# TMC5160A-DRIVER_Rev1.net
KiCad netlist of a schematic drawn in Altium Designer
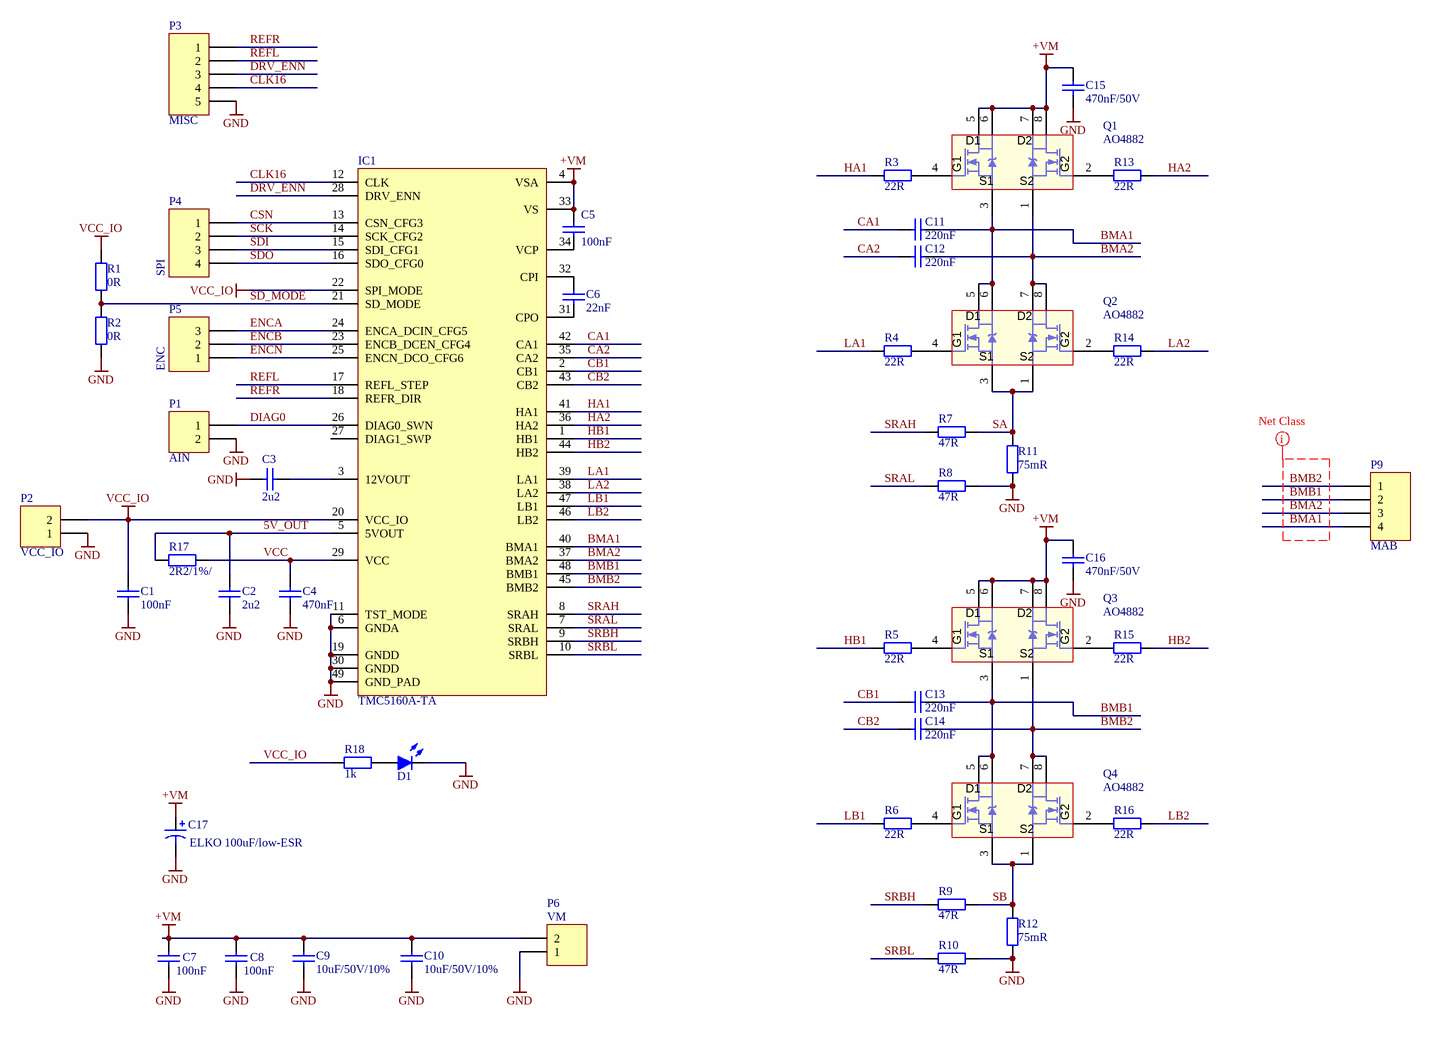
[diagram p0: TMC5160A-DRIVER_Rev1.SchDoc]

(export (version "E")
  (design (tool "Eeschema 10.0.6"))
  (components
    (comp (ref "C1")
      (value "100nF")
      (footprint "C0603")
      (description "Ceramic capacitor")
      (fields (field (name "MANUFACTURER") "Multicomp") (field (name "MPN") "MC0603F104M500CT"))
      (libsource (lib "SCH Passives") (part "Capacitor"))
    )
    (comp (ref "C2")
      (value "2u2")
      (footprint "C0603")
      (description "SMD Multilayer Ceramic Capacitor, 0603 [1608 Metric], 2.2 µF, 25 V, ± 10%, X5R, GRM Series")
      (fields (field (name "MF") "MURATA") (field (name "MPN") "GRM188R61E225KA12D"))
      (libsource (lib "TMC5160_RevA") (part "2.2 µF, 25 V, ± 10%, X5R, GRM Series"))
    )
    (comp (ref "C3")
      (value "2u2")
      (footprint "C0603")
      (description "SMD Multilayer Ceramic Capacitor, 0603 [1608 Metric], 2.2 µF, 25 V, ± 10%, X5R, GRM Series")
      (fields (field (name "MF") "MURATA") (field (name "MPN") "GRM188R61E225KA12D"))
      (libsource (lib "TMC5160_RevA") (part "2.2 µF, 25 V, ± 10%, X5R, GRM Series"))
    )
    (comp (ref "C4")
      (value "470nF")
      (footprint "C0603")
      (description "Ceramic capacitor")
      (fields (field (name "MF") "Multicomp") (field (name "MPN") "MC0603X474K160CT"))
      (libsource (lib "SCH Passives") (part "Capacitor"))
    )
    (comp (ref "C5")
      (value "100nF")
      (footprint "C0603")
      (description "Ceramic capacitor")
      (fields (field (name "MF") "Multicomp") (field (name "MPN") "MC0603F104M500CT"))
      (libsource (lib "SCH Passives") (part "Capacitor"))
    )
    (comp (ref "C6")
      (value "22nF")
      (footprint "C0603")
      (description "Ceramic capacitor")
      (fields (field (name "MF") "Multicomp") (field (name "MPN") "MC0603B223K500CT"))
      (libsource (lib "SCH Passives") (part "Capacitor"))
    )
    (comp (ref "C7")
      (value "100nF")
      (footprint "C0603")
      (description "Ceramic capacitor")
      (fields (field (name "MANUFACTURER") "Multicomp") (field (name "MPN") "MC0603F104M500CT"))
      (libsource (lib "SCH Passives") (part "Capacitor"))
    )
    (comp (ref "C8")
      (value "100nF")
      (footprint "C0603")
      (description "Ceramic capacitor")
      (fields (field (name "MANUFACTURER") "Multicomp") (field (name "MPN") "MC0603F104M500CT"))
      (libsource (lib "SCH Passives") (part "Capacitor"))
    )
    (comp (ref "C9")
      (value "10uF/50V/10%")
      (footprint "C1206")
      (description "SMD Multilayer Ceramic Capacitor, 1206 [3216 Metric], 10 µF, 50 V, ± 20%, X5R, GRM Series")
      (fields (field (name "MF") "MURATA") (field (name "MPN") "GRM31CR61H106MA12L"))
      (libsource (lib "TMC262_FDD8424H_RevA") (part "10 µF, 50 V, ± 20%, X5R, GRM Series"))
    )
    (comp (ref "C10")
      (value "10uF/50V/10%")
      (footprint "C1206")
      (description "SMD Multilayer Ceramic Capacitor, 1206 [3216 Metric], 10 µF, 50 V, ± 20%, X5R, GRM Series")
      (fields (field (name "MF") "MURATA") (field (name "MPN") "GRM31CR61H106MA12L"))
      (libsource (lib "TMC262_FDD8424H_RevA") (part "10 µF, 50 V, ± 20%, X5R, GRM Series"))
    )
    (comp (ref "C11")
      (value "220nF")
      (footprint "C0603")
      (description "SMD Multilayer Ceramic Capacitor, 0603 [1608 Metric], 0.22 µF, 50 V, ± 10%, X7R, GCM Series")
      (fields (field (name "MF") "MURATA") (field (name "MPN") "GCM188R71H224KA64D"))
      (libsource (lib "TMC5160_RevA") (part "0.22 µF, 50 V, ± 10%, X7R"))
    )
    (comp (ref "C12")
      (value "220nF")
      (footprint "C0603")
      (description "SMD Multilayer Ceramic Capacitor, 0603 [1608 Metric], 0.22 µF, 50 V, ± 10%, X7R, GCM Series")
      (fields (field (name "MF") "MURATA") (field (name "MPN") "GCM188R71H224KA64D"))
      (libsource (lib "TMC5160_RevA") (part "0.22 µF, 50 V, ± 10%, X7R"))
    )
    (comp (ref "C13")
      (value "220nF")
      (footprint "C0603")
      (description "SMD Multilayer Ceramic Capacitor, 0603 [1608 Metric], 0.22 µF, 50 V, ± 10%, X7R, GCM Series")
      (fields (field (name "MF") "MURATA") (field (name "MPN") "GCM188R71H224KA64D"))
      (libsource (lib "TMC5160_RevA") (part "0.22 µF, 50 V, ± 10%, X7R"))
    )
    (comp (ref "C14")
      (value "220nF")
      (footprint "C0603")
      (description "SMD Multilayer Ceramic Capacitor, 0603 [1608 Metric], 0.22 µF, 50 V, ± 10%, X7R, GCM Series")
      (fields (field (name "MF") "MURATA") (field (name "MPN") "GCM188R71H224KA64D"))
      (libsource (lib "TMC5160_RevA") (part "0.22 µF, 50 V, ± 10%, X7R"))
    )
    (comp (ref "C15")
      (value "470nF/50V")
      (footprint "C0603")
      (description "SMD Multilayer Ceramic Capacitor, 0603 [1608 Metric], 0.47 µF, 50 V, ± 10%, X7R, C Series")
      (fields (field (name "MF") "TDK") (field (name "MPN") "C1608X7R1H474K080AC"))
      (libsource (lib "TMC5160_RevA") (part "0.47 µF, 50 V, ± 10%, X7R, C Series"))
    )
    (comp (ref "C16")
      (value "470nF/50V")
      (footprint "C0603")
      (description "SMD Multilayer Ceramic Capacitor, 0603 [1608 Metric], 0.47 µF, 50 V, ± 10%, X7R, C Series")
      (fields (field (name "MF") "TDK") (field (name "MPN") "C1608X7R1H474K080AC"))
      (libsource (lib "TMC5160_RevA") (part "0.47 µF, 50 V, ± 10%, X7R, C Series"))
    )
    (comp (ref "C17")
      (value "ELKO 100uF/low-ESR")
      (footprint "EXT_POL_CAP")
      (description "Polarized Capacitor (Radial)")
      (fields (field (name "Comment") "Cap Pol1") (field (name "PUBLISHER") "Altium Limited"))
      (libsource (lib "Miscellaneous Devices") (part "Cap Pol1"))
    )
    (comp (ref "D1")
      (value "LED, Blue, SMD, 20mA, 2.8V, 465 nm")
      (footprint "LED_0603")
      (fields (field (name "MF") "Lite-On") (field (name "MPN") "LTST-C191TBKT-5A"))
      (libsource (lib "TMC26x_RevA") (part "LED, Blue, SMD, 20mA, 2.8V, 465 nm"))
    )
    (comp (ref "IC1")
      (value "TMC5160A-TA")
      (footprint "TMC5160_TSQFP50P900X900X120_HS-49L")
      (fields (field (name "MANUFACTURER") "TRINAMIC"))
      (libsource (lib "TMC5160_BOB_V1_2") (part "TMC5160-TA"))
    )
    (comp (ref "P1")
      (value "AIN")
      (footprint "2_PIN_THT")
      (description "Header, 2-Pin")
      (fields (field (name "PUBLISHER") "Altium Limited"))
      (libsource (lib "Miscellaneous Connectors") (part "Header 2"))
    )
    (comp (ref "P2")
      (value "VCC_IO")
      (footprint "2_PIN_THT")
      (description "Header, 2-Pin")
      (fields (field (name "PUBLISHER") "Altium Limited"))
      (libsource (lib "") (part "Header 2_1"))
    )
    (comp (ref "P3")
      (value "MISC")
      (footprint "5_PIN_THT")
      (description "Header, 5-Pin")
      (fields (field (name "PUBLISHER") "Altium Limited"))
      (libsource (lib "Miscellaneous Connectors") (part "Header 5"))
    )
    (comp (ref "P4")
      (value "SPI")
      (footprint "4_PIN_THT")
      (description "Header, 4-Pin")
      (fields (field (name "PUBLISHER") "Altium Limited"))
      (libsource (lib "Miscellaneous Connectors") (part "Header 4"))
    )
    (comp (ref "P5")
      (value "ENC")
      (footprint "3_PIN_THT")
      (description "Header, 3-Pin")
      (fields (field (name "PUBLISHER") "Altium Limited"))
      (libsource (lib "Miscellaneous Connectors") (part "Header 3"))
    )
    (comp (ref "P6")
      (value "VM")
      (footprint "2_PIN_THT")
      (description "Header, 2-Pin")
      (fields (field (name "PUBLISHER") "Altium Limited"))
      (libsource (lib "") (part "Header 2_2"))
    )
    (comp (ref "P9")
      (value "MAB")
      (footprint "4_PIN_THT_1mm_hole")
      (description "Wire-To-Board Connector, 2.5 mm, 4 Contacts, Header, EH Series, Through Hole, 1 Rows")
      (fields (field (name "MPN") "B4B-EH-A") (field (name "MF") "JST (JAPAN SOLDERLESS TERMINALS)"))
      (libsource (lib "TMC5160_RevA") (part "Wire-To-Board Connector, 2.5 mm, 4 Contacts, Header, EH Series, Through Hole, 1 Rows"))
    )
    (comp (ref "Q1")
      (value "AO4882")
      (footprint "SOP127P600X170-8L")
      (description "Mosfet Array 2 N-Channel (Dual) 40V 8A 2W Surface Mount 8-SOIC")
      (fields (field (name "MF") "Alpha & Omega Semiconductor Inc."))
      (libsource (lib "TMC5160_RevA") (part "AO4882 MOSFET 2N-CH 40V 8A 8SOIC"))
    )
    (comp (ref "Q2")
      (value "AO4882")
      (footprint "SOP127P600X170-8L")
      (description "Mosfet Array 2 N-Channel (Dual) 40V 8A 2W Surface Mount 8-SOIC")
      (fields (field (name "MF") "Alpha & Omega Semiconductor Inc."))
      (libsource (lib "TMC5160_RevA") (part "AO4882 MOSFET 2N-CH 40V 8A 8SOIC"))
    )
    (comp (ref "Q3")
      (value "AO4882")
      (footprint "SOP127P600X170-8L")
      (description "Mosfet Array 2 N-Channel (Dual) 40V 8A 2W Surface Mount 8-SOIC")
      (fields (field (name "MF") "Alpha & Omega Semiconductor Inc."))
      (libsource (lib "TMC5160_RevA") (part "AO4882 MOSFET 2N-CH 40V 8A 8SOIC"))
    )
    (comp (ref "Q4")
      (value "AO4882")
      (footprint "SOP127P600X170-8L")
      (description "Mosfet Array 2 N-Channel (Dual) 40V 8A 2W Surface Mount 8-SOIC")
      (fields (field (name "MF") "Alpha & Omega Semiconductor Inc."))
      (libsource (lib "TMC5160_RevA") (part "AO4882 MOSFET 2N-CH 40V 8A 8SOIC"))
    )
    (comp (ref "R1")
      (value "0R")
      (footprint "R0603")
      (description "SMD Chip Resistor, Thick Film, 0 ohm, 0603 [1608 Metric], 100 mW, MCWR Series")
      (fields
        (field (name "MPN") "MCWR06X000 PTL")
        (field (name "MF") "MULTICOMP")
        (field (name "RESISTANCE") "0R")
      )
      (libsource (lib "TMC5160_RevA") (part "0 ohm, 0603 [1608 Metric], 100 mW, MCWR Series"))
    )
    (comp (ref "R2")
      (value "0R")
      (footprint "R0603")
      (description "SMD Chip Resistor, Thick Film, 0 ohm, 0603 [1608 Metric], 100 mW, MCWR Series")
      (fields
        (field (name "MPN") "MCWR06X000 PTL")
        (field (name "MF") "MULTICOMP")
        (field (name "RESISTANCE") "0R")
      )
      (libsource (lib "TMC5160_RevA") (part "0 ohm, 0603 [1608 Metric], 100 mW, MCWR Series"))
    )
    (comp (ref "R3")
      (value "22R / 100mW / 1%")
      (footprint "R0603")
      (description "SMD Chip Resistor, Thick Film, 22 ohm, 50 V, 0603 [1608 Metric], 100 mW, ± 1%, MCWR Series")
      (fields
        (field (name "MPN") "MCWR06X22R0FTLV")
        (field (name "MF") "MULTICOMP")
        (field (name "RESISTANCE") "22R")
      )
      (libsource (lib "TMC5160_RevA") (part "22 ohm, 50 V, 0603 [1608 Metric], 100 mW, ± 1%, MCWR Series"))
    )
    (comp (ref "R4")
      (value "22R / 100mW / 1%")
      (footprint "R0603")
      (description "SMD Chip Resistor, Thick Film, 22 ohm, 50 V, 0603 [1608 Metric], 100 mW, ± 1%, MCWR Series")
      (fields
        (field (name "MPN") "MCWR06X22R0FTLV")
        (field (name "MF") "MULTICOMP")
        (field (name "RESISTANCE") "22R")
      )
      (libsource (lib "TMC5160_RevA") (part "22 ohm, 50 V, 0603 [1608 Metric], 100 mW, ± 1%, MCWR Series"))
    )
    (comp (ref "R5")
      (value "22R / 100mW / 1%")
      (footprint "R0603")
      (description "SMD Chip Resistor, Thick Film, 22 ohm, 50 V, 0603 [1608 Metric], 100 mW, ± 1%, MCWR Series")
      (fields
        (field (name "MPN") "MCWR06X22R0FTLV")
        (field (name "MF") "MULTICOMP")
        (field (name "RESISTANCE") "22R")
      )
      (libsource (lib "TMC5160_RevA") (part "22 ohm, 50 V, 0603 [1608 Metric], 100 mW, ± 1%, MCWR Series"))
    )
    (comp (ref "R6")
      (value "22R / 100mW / 1%")
      (footprint "R0603")
      (description "SMD Chip Resistor, Thick Film, 22 ohm, 50 V, 0603 [1608 Metric], 100 mW, ± 1%, MCWR Series")
      (fields
        (field (name "MPN") "MCWR06X22R0FTLV")
        (field (name "MF") "MULTICOMP")
        (field (name "RESISTANCE") "22R")
      )
      (libsource (lib "TMC5160_RevA") (part "22 ohm, 50 V, 0603 [1608 Metric], 100 mW, ± 1%, MCWR Series"))
    )
    (comp (ref "R7")
      (value "47R /  / 1%")
      (footprint "R0603")
      (description "SMD Chip Resistor, Ceramic, 47 ohm, 75 V, 0603 [1608 Metric], 100 mW, ± 1%, MCSR 06 Series")
      (fields
        (field (name "MPN") "MCSR06X47R0FTL")
        (field (name "MF") "MULTICOMP")
        (field (name "RESISTANCE") "47R")
      )
      (libsource (lib "TMC5160_RevA") (part "47 ohm, 75 V, 0603 [1608 Metric], 100 mW, ± 1%, MCSR 06 Series"))
    )
    (comp (ref "R8")
      (value "47R /  / 1%")
      (footprint "R0603")
      (description "SMD Chip Resistor, Ceramic, 47 ohm, 75 V, 0603 [1608 Metric], 100 mW, ± 1%, MCSR 06 Series")
      (fields
        (field (name "MPN") "MCSR06X47R0FTL")
        (field (name "MF") "MULTICOMP")
        (field (name "RESISTANCE") "47R")
      )
      (libsource (lib "TMC5160_RevA") (part "47 ohm, 75 V, 0603 [1608 Metric], 100 mW, ± 1%, MCSR 06 Series"))
    )
    (comp (ref "R9")
      (value "47R /  / 1%")
      (footprint "R0603")
      (description "SMD Chip Resistor, Ceramic, 47 ohm, 75 V, 0603 [1608 Metric], 100 mW, ± 1%, MCSR 06 Series")
      (fields
        (field (name "MPN") "MCSR06X47R0FTL")
        (field (name "MF") "MULTICOMP")
        (field (name "RESISTANCE") "47R")
      )
      (libsource (lib "TMC5160_RevA") (part "47 ohm, 75 V, 0603 [1608 Metric], 100 mW, ± 1%, MCSR 06 Series"))
    )
    (comp (ref "R10")
      (value "47R /  / 1%")
      (footprint "R0603")
      (description "SMD Chip Resistor, Ceramic, 47 ohm, 75 V, 0603 [1608 Metric], 100 mW, ± 1%, MCSR 06 Series")
      (fields
        (field (name "MPN") "MCSR06X47R0FTL")
        (field (name "MF") "MULTICOMP")
        (field (name "RESISTANCE") "47R")
      )
      (libsource (lib "TMC5160_RevA") (part "47 ohm, 75 V, 0603 [1608 Metric], 100 mW, ± 1%, MCSR 06 Series"))
    )
    (comp (ref "R11")
      (value "75mR")
      (footprint "R1206")
      (description "SMD Chip Resistor, Thick Film, Current Sense Resistors - SMD 1W 0.075ohm 1%")
      (fields
        (field (name "MPN") "ERJ-8BWFR075V")
        (field (name "MF") "Panasonic Electronic Components")
        (field (name "RESISTANCE") "75mR")
      )
      (libsource (lib "SMD_Passives") (part "R_SENS, 0.075 ohm, 1206, 1W, ± 1%, ERJ Series"))
    )
    (comp (ref "R12")
      (value "75mR")
      (footprint "R1206")
      (description "SMD Chip Resistor, Thick Film, Current Sense Resistors - SMD 1W 0.075ohm 1%")
      (fields
        (field (name "MPN") "ERJ-8BWFR075V")
        (field (name "MF") "Panasonic Electronic Components")
        (field (name "RESISTANCE") "75mR")
      )
      (libsource (lib "SMD_Passives") (part "R_SENS, 0.075 ohm, 1206, 1W, ± 1%, ERJ Series"))
    )
    (comp (ref "R13")
      (value "22R / 100mW / 1%")
      (footprint "R0603")
      (description "SMD Chip Resistor, Thick Film, 22 ohm, 50 V, 0603 [1608 Metric], 100 mW, ± 1%, MCWR Series")
      (fields
        (field (name "MPN") "MCWR06X22R0FTLV")
        (field (name "MF") "MULTICOMP")
        (field (name "RESISTANCE") "22R")
      )
      (libsource (lib "TMC5160_RevA") (part "22 ohm, 50 V, 0603 [1608 Metric], 100 mW, ± 1%, MCWR Series"))
    )
    (comp (ref "R14")
      (value "22R / 100mW / 1%")
      (footprint "R0603")
      (description "SMD Chip Resistor, Thick Film, 22 ohm, 50 V, 0603 [1608 Metric], 100 mW, ± 1%, MCWR Series")
      (fields
        (field (name "MPN") "MCWR06X22R0FTLV")
        (field (name "MF") "MULTICOMP")
        (field (name "RESISTANCE") "22R")
      )
      (libsource (lib "TMC5160_RevA") (part "22 ohm, 50 V, 0603 [1608 Metric], 100 mW, ± 1%, MCWR Series"))
    )
    (comp (ref "R15")
      (value "22R / 100mW / 1%")
      (footprint "R0603")
      (description "SMD Chip Resistor, Thick Film, 22 ohm, 50 V, 0603 [1608 Metric], 100 mW, ± 1%, MCWR Series")
      (fields
        (field (name "MPN") "MCWR06X22R0FTLV")
        (field (name "MF") "MULTICOMP")
        (field (name "RESISTANCE") "22R")
      )
      (libsource (lib "TMC5160_RevA") (part "22 ohm, 50 V, 0603 [1608 Metric], 100 mW, ± 1%, MCWR Series"))
    )
    (comp (ref "R16")
      (value "22R / 100mW / 1%")
      (footprint "R0603")
      (description "SMD Chip Resistor, Thick Film, 22 ohm, 50 V, 0603 [1608 Metric], 100 mW, ± 1%, MCWR Series")
      (fields
        (field (name "MPN") "MCWR06X22R0FTLV")
        (field (name "MF") "MULTICOMP")
        (field (name "RESISTANCE") "22R")
      )
      (libsource (lib "TMC5160_RevA") (part "22 ohm, 50 V, 0603 [1608 Metric], 100 mW, ± 1%, MCWR Series"))
    )
    (comp (ref "R17")
      (value "2R2/1%/")
      (footprint "R0603")
      (description "Resistor")
      (fields (field (name "MPN") "MC0063W060312R2") (field (name "MF") "Multicomp"))
      (libsource (lib "SCH Passives") (part "Resistor"))
    )
    (comp (ref "R18")
      (value "1k")
      (footprint "R0603")
      (description "1 kohm, 50 V, 0603 [1608 Metric], 63 mW, ± 1%, MC Series")
      (fields
        (field (name "MPN") "MC0063W060311K")
        (field (name "MF") "MULTICOMP")
        (field (name "RESISTANCE") "1k")
      )
      (libsource (lib "TMC457_RevA") (part "1 kohm, 50 V, 0603 [1608 Metric], 63 mW, ± 1%, MC Series"))
    )
  )
  (nets
    (net (code "1") (name "+VM") (class "Default")
      (node (ref "C10") (pin "2") (pinfunction "2_2") (pintype "passive"))
      (node (ref "C15") (pin "1") (pinfunction "1_1") (pintype "passive"))
      (node (ref "C16") (pin "1") (pinfunction "1_1") (pintype "passive"))
      (node (ref "C17") (pin "1") (pinfunction "1_1") (pintype "passive"))
      (node (ref "C5") (pin "1") (pinfunction "1_1") (pintype "passive"))
      (node (ref "C7") (pin "1") (pinfunction "1_1") (pintype "passive"))
      (node (ref "C8") (pin "1") (pinfunction "1_1") (pintype "passive"))
      (node (ref "C9") (pin "2") (pinfunction "2_2") (pintype "passive"))
      (node (ref "IC1") (pin "33") (pinfunction "VS_33") (pintype "passive"))
      (node (ref "IC1") (pin "4") (pinfunction "VSA_4") (pintype "passive"))
      (node (ref "P6") (pin "2") (pinfunction "2_2") (pintype "passive"))
      (node (ref "Q1") (pin "5") (pinfunction "D1_5") (pintype "passive"))
      (node (ref "Q1") (pin "6") (pinfunction "D1_6") (pintype "passive"))
      (node (ref "Q1") (pin "7") (pinfunction "D2_7") (pintype "passive"))
      (node (ref "Q1") (pin "8") (pinfunction "D2_8") (pintype "passive"))
      (node (ref "Q3") (pin "5") (pinfunction "D1_5") (pintype "passive"))
      (node (ref "Q3") (pin "6") (pinfunction "D1_6") (pintype "passive"))
      (node (ref "Q3") (pin "7") (pinfunction "D2_7") (pintype "passive"))
      (node (ref "Q3") (pin "8") (pinfunction "D2_8") (pintype "passive"))
    )
    (net (code "2") (name "/5V_OUT") (class "Default")
      (node (ref "C2") (pin "1") (pinfunction "1_1") (pintype "passive"))
      (node (ref "IC1") (pin "5") (pinfunction "5VOUT_5") (pintype "passive"))
      (node (ref "R17") (pin "1") (pinfunction "1_1") (pintype "passive"))
    )
    (net (code "3") (name "/BMA1") (class "Default")
      (node (ref "C11") (pin "2") (pinfunction "2_2") (pintype "passive"))
      (node (ref "IC1") (pin "40") (pinfunction "BMA1_40") (pintype "passive"))
      (node (ref "P9") (pin "4") (pinfunction "4_4") (pintype "passive"))
      (node (ref "Q1") (pin "3") (pinfunction "S1_3") (pintype "passive"))
      (node (ref "Q2") (pin "5") (pinfunction "D1_5") (pintype "passive"))
      (node (ref "Q2") (pin "6") (pinfunction "D1_6") (pintype "passive"))
    )
    (net (code "4") (name "/BMA2") (class "Default")
      (node (ref "C12") (pin "2") (pinfunction "2_2") (pintype "passive"))
      (node (ref "IC1") (pin "37") (pinfunction "BMA2_37") (pintype "passive"))
      (node (ref "P9") (pin "3") (pinfunction "3_3") (pintype "passive"))
      (node (ref "Q1") (pin "1") (pinfunction "S2_1") (pintype "passive"))
      (node (ref "Q2") (pin "7") (pinfunction "D2_7") (pintype "passive"))
      (node (ref "Q2") (pin "8") (pinfunction "D2_8") (pintype "passive"))
    )
    (net (code "5") (name "/BMB1") (class "Default")
      (node (ref "C13") (pin "2") (pinfunction "2_2") (pintype "passive"))
      (node (ref "IC1") (pin "48") (pinfunction "BMB1_48") (pintype "passive"))
      (node (ref "P9") (pin "2") (pinfunction "2_2") (pintype "passive"))
      (node (ref "Q3") (pin "3") (pinfunction "S1_3") (pintype "passive"))
      (node (ref "Q4") (pin "5") (pinfunction "D1_5") (pintype "passive"))
      (node (ref "Q4") (pin "6") (pinfunction "D1_6") (pintype "passive"))
    )
    (net (code "6") (name "/BMB2") (class "Default")
      (node (ref "C14") (pin "2") (pinfunction "2_2") (pintype "passive"))
      (node (ref "IC1") (pin "45") (pinfunction "BMB2_45") (pintype "passive"))
      (node (ref "P9") (pin "1") (pinfunction "1_1") (pintype "passive"))
      (node (ref "Q3") (pin "1") (pinfunction "S2_1") (pintype "passive"))
      (node (ref "Q4") (pin "7") (pinfunction "D2_7") (pintype "passive"))
      (node (ref "Q4") (pin "8") (pinfunction "D2_8") (pintype "passive"))
    )
    (net (code "7") (name "/CA1") (class "Default")
      (node (ref "C11") (pin "1") (pinfunction "1_1") (pintype "passive"))
      (node (ref "IC1") (pin "42") (pinfunction "CA1_42") (pintype "passive"))
    )
    (net (code "8") (name "/CA2") (class "Default")
      (node (ref "C12") (pin "1") (pinfunction "1_1") (pintype "passive"))
      (node (ref "IC1") (pin "35") (pinfunction "CA2_35") (pintype "passive"))
    )
    (net (code "9") (name "/CB1") (class "Default")
      (node (ref "C13") (pin "1") (pinfunction "1_1") (pintype "passive"))
      (node (ref "IC1") (pin "2") (pinfunction "CB1_2") (pintype "passive"))
    )
    (net (code "10") (name "/CB2") (class "Default")
      (node (ref "C14") (pin "1") (pinfunction "1_1") (pintype "passive"))
      (node (ref "IC1") (pin "43") (pinfunction "CB2_43") (pintype "passive"))
    )
    (net (code "11") (name "/CLK16") (class "Default")
      (node (ref "IC1") (pin "12") (pinfunction "CLK_12") (pintype "passive"))
      (node (ref "P3") (pin "4") (pinfunction "4_4") (pintype "passive"))
    )
    (net (code "12") (name "/CSN") (class "Default")
      (node (ref "IC1") (pin "13") (pinfunction "CSN_CFG3_13") (pintype "passive"))
      (node (ref "P4") (pin "1") (pinfunction "1_1") (pintype "passive"))
    )
    (net (code "13") (name "/DIAG0") (class "Default")
      (node (ref "IC1") (pin "26") (pinfunction "DIAG0_SWN_26") (pintype "passive"))
      (node (ref "P1") (pin "1") (pinfunction "1_1") (pintype "passive"))
    )
    (net (code "14") (name "/DRV_ENN") (class "Default")
      (node (ref "IC1") (pin "28") (pinfunction "DRV_ENN_28") (pintype "passive"))
      (node (ref "P3") (pin "3") (pinfunction "3_3") (pintype "passive"))
    )
    (net (code "15") (name "/ENCA") (class "Default")
      (node (ref "IC1") (pin "24") (pinfunction "ENCA_DCIN_CFG5_24") (pintype "passive"))
      (node (ref "P5") (pin "3") (pinfunction "3_3") (pintype "passive"))
    )
    (net (code "16") (name "/ENCB") (class "Default")
      (node (ref "IC1") (pin "23") (pinfunction "ENCB_DCEN_CFG4_23") (pintype "passive"))
      (node (ref "P5") (pin "2") (pinfunction "2_2") (pintype "passive"))
    )
    (net (code "17") (name "/ENCN") (class "Default")
      (node (ref "IC1") (pin "25") (pinfunction "ENCN_DCO_CFG6_25") (pintype "passive"))
      (node (ref "P5") (pin "1") (pinfunction "1_1") (pintype "passive"))
    )
    (net (code "18") (name "/HA1") (class "Default")
      (node (ref "IC1") (pin "41") (pinfunction "HA1_41") (pintype "passive"))
      (node (ref "R3") (pin "2") (pinfunction "2_2") (pintype "passive"))
    )
    (net (code "19") (name "/HA2") (class "Default")
      (node (ref "IC1") (pin "36") (pinfunction "HA2_36") (pintype "passive"))
      (node (ref "R13") (pin "1") (pinfunction "1_1") (pintype "passive"))
    )
    (net (code "20") (name "/HB1") (class "Default")
      (node (ref "IC1") (pin "1") (pinfunction "HB1_1") (pintype "passive"))
      (node (ref "R5") (pin "2") (pinfunction "2_2") (pintype "passive"))
    )
    (net (code "21") (name "/HB2") (class "Default")
      (node (ref "IC1") (pin "44") (pinfunction "HB2_44") (pintype "passive"))
      (node (ref "R15") (pin "1") (pinfunction "1_1") (pintype "passive"))
    )
    (net (code "22") (name "/LA1") (class "Default")
      (node (ref "IC1") (pin "39") (pinfunction "LA1_39") (pintype "passive"))
      (node (ref "R4") (pin "2") (pinfunction "2_2") (pintype "passive"))
    )
    (net (code "23") (name "/LA2") (class "Default")
      (node (ref "IC1") (pin "38") (pinfunction "LA2_38") (pintype "passive"))
      (node (ref "R14") (pin "1") (pinfunction "1_1") (pintype "passive"))
    )
    (net (code "24") (name "/LB1") (class "Default")
      (node (ref "IC1") (pin "47") (pinfunction "LB1_47") (pintype "passive"))
      (node (ref "R6") (pin "2") (pinfunction "2_2") (pintype "passive"))
    )
    (net (code "25") (name "/LB2") (class "Default")
      (node (ref "IC1") (pin "46") (pinfunction "LB2_46") (pintype "passive"))
      (node (ref "R16") (pin "1") (pinfunction "1_1") (pintype "passive"))
    )
    (net (code "26") (name "/REFL") (class "Default")
      (node (ref "IC1") (pin "17") (pinfunction "REFL_STEP_17") (pintype "passive"))
      (node (ref "P3") (pin "2") (pinfunction "2_2") (pintype "passive"))
    )
    (net (code "27") (name "/REFR") (class "Default")
      (node (ref "IC1") (pin "18") (pinfunction "REFR_DIR_18") (pintype "passive"))
      (node (ref "P3") (pin "1") (pinfunction "1_1") (pintype "passive"))
    )
    (net (code "28") (name "/SA") (class "Default")
      (node (ref "Q2") (pin "1") (pinfunction "S2_1") (pintype "passive"))
      (node (ref "Q2") (pin "3") (pinfunction "S1_3") (pintype "passive"))
      (node (ref "R11") (pin "1") (pinfunction "1_1") (pintype "passive"))
      (node (ref "R7") (pin "1") (pinfunction "1_1") (pintype "passive"))
    )
    (net (code "29") (name "/SB") (class "Default")
      (node (ref "Q4") (pin "1") (pinfunction "S2_1") (pintype "passive"))
      (node (ref "Q4") (pin "3") (pinfunction "S1_3") (pintype "passive"))
      (node (ref "R12") (pin "1") (pinfunction "1_1") (pintype "passive"))
      (node (ref "R9") (pin "1") (pinfunction "1_1") (pintype "passive"))
    )
    (net (code "30") (name "/SCK") (class "Default")
      (node (ref "IC1") (pin "14") (pinfunction "SCK_CFG2_14") (pintype "passive"))
      (node (ref "P4") (pin "2") (pinfunction "2_2") (pintype "passive"))
    )
    (net (code "31") (name "/SDI") (class "Default")
      (node (ref "IC1") (pin "15") (pinfunction "SDI_CFG1_15") (pintype "passive"))
      (node (ref "P4") (pin "3") (pinfunction "3_3") (pintype "passive"))
    )
    (net (code "32") (name "/SDO") (class "Default")
      (node (ref "IC1") (pin "16") (pinfunction "SDO_CFG0_16") (pintype "passive"))
      (node (ref "P4") (pin "4") (pinfunction "4_4") (pintype "passive"))
    )
    (net (code "33") (name "/SD_MODE") (class "Default")
      (node (ref "IC1") (pin "21") (pinfunction "SD_MODE_21") (pintype "passive"))
      (node (ref "R1") (pin "2") (pinfunction "2_2") (pintype "passive"))
      (node (ref "R2") (pin "1") (pinfunction "1_1") (pintype "passive"))
    )
    (net (code "34") (name "/SRAH") (class "Default")
      (node (ref "IC1") (pin "8") (pinfunction "SRAH_8") (pintype "passive"))
      (node (ref "R7") (pin "2") (pinfunction "2_2") (pintype "passive"))
    )
    (net (code "35") (name "/SRAL") (class "Default")
      (node (ref "IC1") (pin "7") (pinfunction "SRAL_7") (pintype "passive"))
      (node (ref "R8") (pin "2") (pinfunction "2_2") (pintype "passive"))
    )
    (net (code "36") (name "/SRBH") (class "Default")
      (node (ref "IC1") (pin "9") (pinfunction "SRBH_9") (pintype "passive"))
      (node (ref "R9") (pin "2") (pinfunction "2_2") (pintype "passive"))
    )
    (net (code "37") (name "/SRBL") (class "Default")
      (node (ref "IC1") (pin "10") (pinfunction "SRBL_10") (pintype "passive"))
      (node (ref "R10") (pin "2") (pinfunction "2_2") (pintype "passive"))
    )
    (net (code "38") (name "/VCC") (class "Default")
      (node (ref "C4") (pin "1") (pinfunction "1_1") (pintype "passive"))
      (node (ref "IC1") (pin "29") (pinfunction "VCC_29") (pintype "passive"))
      (node (ref "R17") (pin "2") (pinfunction "2_2") (pintype "passive"))
    )
    (net (code "39") (name "GND") (class "Default")
      (node (ref "C1") (pin "2") (pinfunction "2_2") (pintype "passive"))
      (node (ref "C10") (pin "1") (pinfunction "1_1") (pintype "passive"))
      (node (ref "C15") (pin "2") (pinfunction "2_2") (pintype "passive"))
      (node (ref "C16") (pin "2") (pinfunction "2_2") (pintype "passive"))
      (node (ref "C17") (pin "2") (pinfunction "2_2") (pintype "passive"))
      (node (ref "C2") (pin "2") (pinfunction "2_2") (pintype "passive"))
      (node (ref "C3") (pin "1") (pinfunction "1_1") (pintype "passive"))
      (node (ref "C4") (pin "2") (pinfunction "2_2") (pintype "passive"))
      (node (ref "C7") (pin "2") (pinfunction "2_2") (pintype "passive"))
      (node (ref "C8") (pin "2") (pinfunction "2_2") (pintype "passive"))
      (node (ref "C9") (pin "1") (pinfunction "1_1") (pintype "passive"))
      (node (ref "D1") (pin "2") (pinfunction "K_2") (pintype "passive"))
      (node (ref "IC1") (pin "11") (pinfunction "TST_MODE_11") (pintype "passive"))
      (node (ref "IC1") (pin "19") (pinfunction "GNDD_19") (pintype "passive"))
      (node (ref "IC1") (pin "30") (pinfunction "GNDD_30") (pintype "passive"))
      (node (ref "IC1") (pin "49") (pinfunction "GND_PAD_49") (pintype "passive"))
      (node (ref "IC1") (pin "6") (pinfunction "GNDA_6") (pintype "passive"))
      (node (ref "P1") (pin "2") (pinfunction "2_2") (pintype "passive"))
      (node (ref "P2") (pin "1") (pinfunction "1_1") (pintype "passive"))
      (node (ref "P3") (pin "5") (pinfunction "5_5") (pintype "passive"))
      (node (ref "P6") (pin "1") (pinfunction "1_1") (pintype "passive"))
      (node (ref "R10") (pin "1") (pinfunction "1_1") (pintype "passive"))
      (node (ref "R11") (pin "2") (pinfunction "2_2") (pintype "passive"))
      (node (ref "R12") (pin "2") (pinfunction "2_2") (pintype "passive"))
      (node (ref "R2") (pin "2") (pinfunction "2_2") (pintype "passive"))
      (node (ref "R8") (pin "1") (pinfunction "1_1") (pintype "passive"))
    )
    (net (code "40") (name "Net-(D1-A)") (class "Default")
      (node (ref "D1") (pin "1") (pinfunction "A_1") (pintype "passive"))
      (node (ref "R18") (pin "2") (pinfunction "2_2") (pintype "passive"))
    )
    (net (code "41") (name "Net-(IC1-12VOUT)") (class "Default")
      (node (ref "C3") (pin "2") (pinfunction "2_2") (pintype "passive"))
      (node (ref "IC1") (pin "3") (pinfunction "12VOUT_3") (pintype "passive"))
    )
    (net (code "42") (name "Net-(IC1-CPI)") (class "Default")
      (node (ref "C6") (pin "2") (pinfunction "2_2") (pintype "passive"))
      (node (ref "IC1") (pin "32") (pinfunction "CPI_32") (pintype "passive"))
    )
    (net (code "43") (name "Net-(IC1-CPO)") (class "Default")
      (node (ref "C6") (pin "1") (pinfunction "1_1") (pintype "passive"))
      (node (ref "IC1") (pin "31") (pinfunction "CPO_31") (pintype "passive"))
    )
    (net (code "44") (name "Net-(IC1-VCP)") (class "Default")
      (node (ref "C5") (pin "2") (pinfunction "2_2") (pintype "passive"))
      (node (ref "IC1") (pin "34") (pinfunction "VCP_34") (pintype "passive"))
    )
    (net (code "45") (name "Net-(Q1-G1)") (class "Default")
      (node (ref "Q1") (pin "4") (pinfunction "G1_4") (pintype "passive"))
      (node (ref "R3") (pin "1") (pinfunction "1_1") (pintype "passive"))
    )
    (net (code "46") (name "Net-(Q1-G2)") (class "Default")
      (node (ref "Q1") (pin "2") (pinfunction "G2_2") (pintype "passive"))
      (node (ref "R13") (pin "2") (pinfunction "2_2") (pintype "passive"))
    )
    (net (code "47") (name "Net-(Q2-G1)") (class "Default")
      (node (ref "Q2") (pin "4") (pinfunction "G1_4") (pintype "passive"))
      (node (ref "R4") (pin "1") (pinfunction "1_1") (pintype "passive"))
    )
    (net (code "48") (name "Net-(Q2-G2)") (class "Default")
      (node (ref "Q2") (pin "2") (pinfunction "G2_2") (pintype "passive"))
      (node (ref "R14") (pin "2") (pinfunction "2_2") (pintype "passive"))
    )
    (net (code "49") (name "Net-(Q3-G1)") (class "Default")
      (node (ref "Q3") (pin "4") (pinfunction "G1_4") (pintype "passive"))
      (node (ref "R5") (pin "1") (pinfunction "1_1") (pintype "passive"))
    )
    (net (code "50") (name "Net-(Q3-G2)") (class "Default")
      (node (ref "Q3") (pin "2") (pinfunction "G2_2") (pintype "passive"))
      (node (ref "R15") (pin "2") (pinfunction "2_2") (pintype "passive"))
    )
    (net (code "51") (name "Net-(Q4-G1)") (class "Default")
      (node (ref "Q4") (pin "4") (pinfunction "G1_4") (pintype "passive"))
      (node (ref "R6") (pin "1") (pinfunction "1_1") (pintype "passive"))
    )
    (net (code "52") (name "Net-(Q4-G2)") (class "Default")
      (node (ref "Q4") (pin "2") (pinfunction "G2_2") (pintype "passive"))
      (node (ref "R16") (pin "2") (pinfunction "2_2") (pintype "passive"))
    )
    (net (code "53") (name "VCC_IO") (class "Default")
      (node (ref "C1") (pin "1") (pinfunction "1_1") (pintype "passive"))
      (node (ref "IC1") (pin "20") (pinfunction "VCC_IO_20") (pintype "passive"))
      (node (ref "IC1") (pin "22") (pinfunction "SPI_MODE_22") (pintype "passive"))
      (node (ref "P2") (pin "2") (pinfunction "2_2") (pintype "passive"))
      (node (ref "R1") (pin "1") (pinfunction "1_1") (pintype "passive"))
      (node (ref "R18") (pin "1") (pinfunction "1_1") (pintype "passive"))
    )
    (net (code "54") (name "unconnected-(IC1-DIAG1_SWP-Pad27)") (class "Default")
      (node (ref "IC1") (pin "27") (pinfunction "DIAG1_SWP_27") (pintype "passive"))
    )
  )
)
